# main.net
KiCad netlist of a schematic drawn in EAGLE
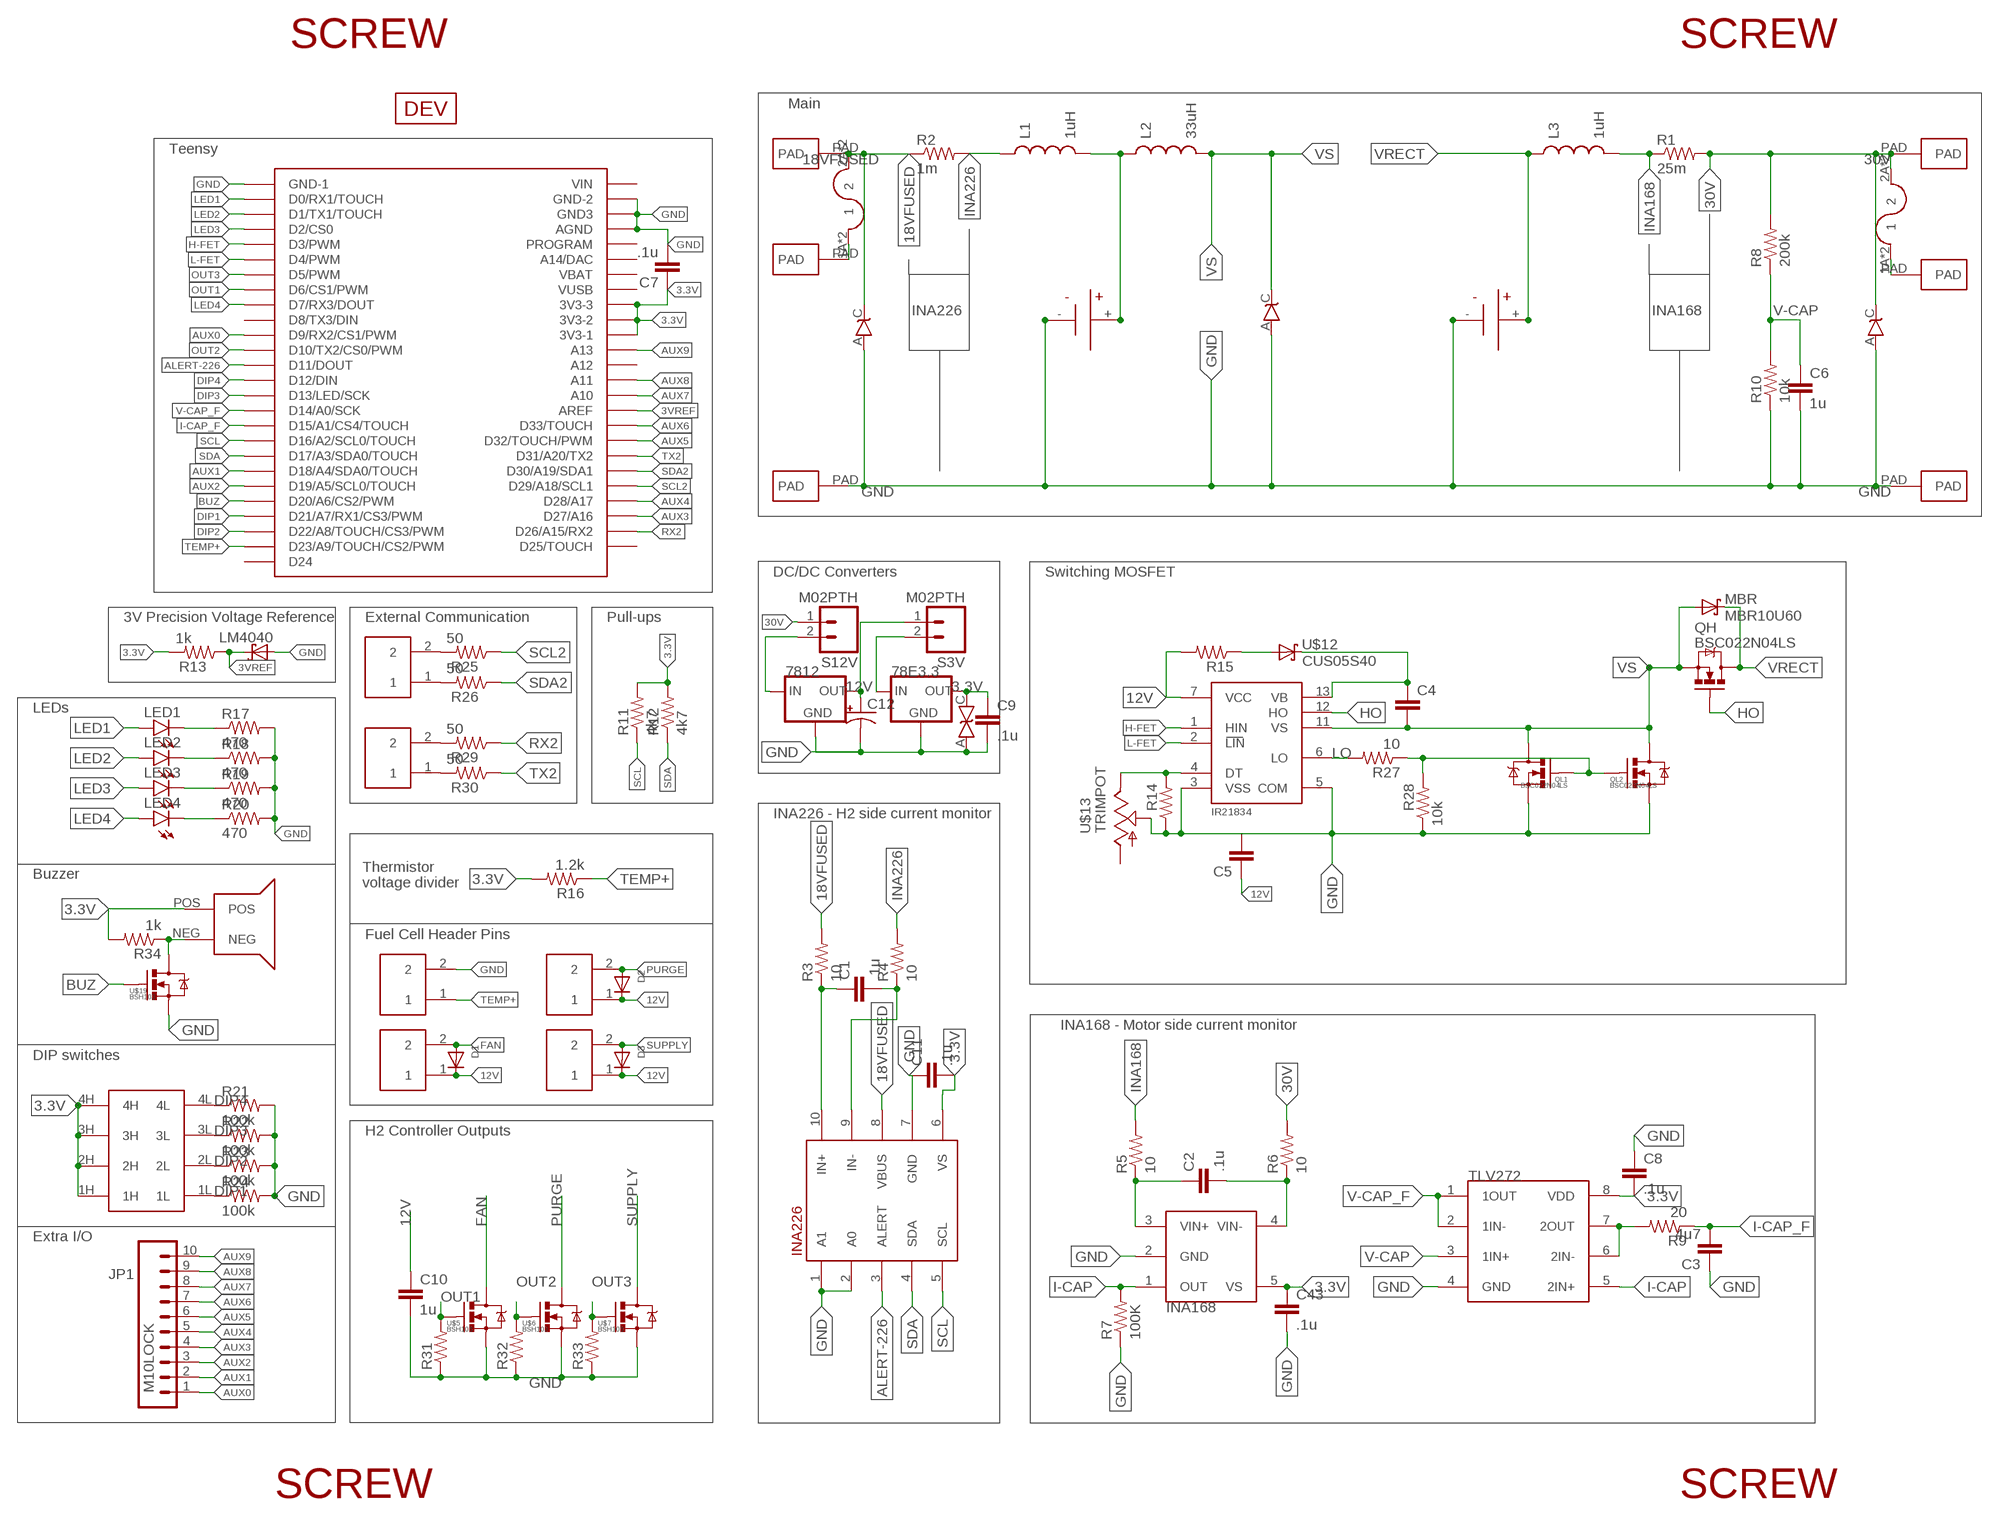
[diagram p0: schematic, sheet 1]

(export (version "E")
  (design (tool "Eeschema 10.0.6"))
  (components
    (comp (ref "78E3.3")
      (value "V_REG_78XXR-78E")
      (footprint "eagle-import:V78W")
      (libsource (lib "eagle-import") (part "V_REG_78XXR-78E"))
    )
    (comp (ref "7812")
      (value "V_REG_78XX")
      (footprint "eagle-import:V78W_BACKWARDS")
      (libsource (lib "eagle-import") (part "V_REG_78XX"))
    )
    (comp (ref "C1")
      (value ".1u")
      (footprint "eagle-import:0603-CAP")
      (libsource (lib "eagle-import") (part "CAP0603-CAP"))
    )
    (comp (ref "C1-1")
      (value "2400u")
      (footprint "eagle-import:CAP-RADIAL")
      (libsource (lib "eagle-import") (part "CAP-AL_ELECTROLYTIC"))
    )
    (comp (ref "C2")
      (value ".1u")
      (footprint "eagle-import:0603-CAP")
      (libsource (lib "eagle-import") (part "CAP0603-CAP"))
    )
    (comp (ref "C2-1")
      (value "2400u")
      (footprint "eagle-import:CAP-RADIAL")
      (libsource (lib "eagle-import") (part "CAP-AL_ELECTROLYTIC"))
    )
    (comp (ref "C3")
      (value "4u7")
      (footprint "eagle-import:0603-CAP")
      (libsource (lib "eagle-import") (part "CAP0603-CAP"))
    )
    (comp (ref "C4")
      (value "CAP0603-CAP")
      (footprint "eagle-import:0603-CAP")
      (libsource (lib "eagle-import") (part "CAP0603-CAP"))
    )
    (comp (ref "C5")
      (value "CAP0603-CAP")
      (footprint "eagle-import:0603-CAP")
      (libsource (lib "eagle-import") (part "CAP0603-CAP"))
    )
    (comp (ref "C6")
      (value "1u")
      (footprint "eagle-import:0603-CAP")
      (libsource (lib "eagle-import") (part "CAP0603-CAP"))
    )
    (comp (ref "C7")
      (value ".1u")
      (footprint "eagle-import:0603-CAP")
      (libsource (lib "eagle-import") (part "CAP0603-CAP"))
    )
    (comp (ref "C8")
      (value ".1u")
      (footprint "eagle-import:0603-CAP")
      (libsource (lib "eagle-import") (part "CAP0603-CAP"))
    )
    (comp (ref "C9")
      (value ".1u")
      (footprint "eagle-import:0603-CAP")
      (libsource (lib "eagle-import") (part "CAP0603-CAP"))
    )
    (comp (ref "C10")
      (value "1u")
      (footprint "eagle-import:0603-CAP")
      (libsource (lib "eagle-import") (part "CAP0603-CAP"))
    )
    (comp (ref "C11")
      (value ".1u")
      (footprint "eagle-import:0603-CAP")
      (libsource (lib "eagle-import") (part "CAP0603-CAP"))
    )
    (comp (ref "C12")
      (value "10UF-25V-20%(PTH)")
      (footprint "eagle-import:CPOL-RADIAL-10UF-25V")
      (libsource (lib "eagle-import") (part "10UF-25V-20%(PTH)"))
    )
    (comp (ref "C43")
      (value ".1u")
      (footprint "eagle-import:0603-CAP")
      (libsource (lib "eagle-import") (part "CAP0603-CAP"))
    )
    (comp (ref "D1")
      (value "DIODESOT23_REFLOW")
      (footprint "eagle-import:SOT23-R")
      (libsource (lib "eagle-import") (part "DIODESOT23_REFLOW"))
    )
    (comp (ref "D2")
      (value "DIODESOT23_REFLOW")
      (footprint "eagle-import:SOT23-R")
      (libsource (lib "eagle-import") (part "DIODESOT23_REFLOW"))
    )
    (comp (ref "D3")
      (value "DIODESOT23_REFLOW")
      (footprint "eagle-import:SOT23-R")
      (libsource (lib "eagle-import") (part "DIODESOT23_REFLOW"))
    )
    (comp (ref "FAN")
      (value "HEADER2")
      (footprint "eagle-import:2PINVALULOK")
      (libsource (lib "eagle-import") (part "HEADER2"))
    )
    (comp (ref "I2C")
      (value "HEADER2")
      (footprint "eagle-import:2PINVALULOK")
      (libsource (lib "eagle-import") (part "HEADER2"))
    )
    (comp (ref "INFUSE")
      (value "FUSE")
      (footprint "eagle-import:AUTO_FUSE")
      (libsource (lib "eagle-import") (part "FUSE"))
    )
    (comp (ref "JP1")
      (value "M10LOCK")
      (footprint "eagle-import:1X10_LOCK")
      (libsource (lib "eagle-import") (part "M10LOCK"))
    )
    (comp (ref "L1")
      (value "1uH")
      (footprint "eagle-import:SER20XX")
      (libsource (lib "eagle-import") (part "INDUCTORSER2010-102"))
    )
    (comp (ref "L2")
      (value "33uH")
      (footprint "eagle-import:D1787")
      (libsource (lib "eagle-import") (part "D1787-AL"))
    )
    (comp (ref "L3")
      (value "1uH")
      (footprint "eagle-import:SER20XX")
      (libsource (lib "eagle-import") (part "INDUCTORSER2010-102"))
    )
    (comp (ref "LED1")
      (value "LED0603")
      (footprint "eagle-import:LED-0603")
      (libsource (lib "eagle-import") (part "LED0603"))
    )
    (comp (ref "LED2")
      (value "LED0603")
      (footprint "eagle-import:LED-0603")
      (libsource (lib "eagle-import") (part "LED0603"))
    )
    (comp (ref "LED3")
      (value "LED0603")
      (footprint "eagle-import:LED-0603")
      (libsource (lib "eagle-import") (part "LED0603"))
    )
    (comp (ref "LED4")
      (value "LED0603")
      (footprint "eagle-import:LED-0603")
      (libsource (lib "eagle-import") (part "LED0603"))
    )
    (comp (ref "MBR")
      (value "MBR10U60")
      (footprint "eagle-import:TO-277")
      (libsource (lib "eagle-import") (part "MBR10U60"))
    )
    (comp (ref "OUTFUSE")
      (value "FUSE")
      (footprint "eagle-import:AUTO_FUSE")
      (libsource (lib "eagle-import") (part "FUSE"))
    )
    (comp (ref "PURGEVALVE")
      (value "HEADER2")
      (footprint "eagle-import:2PINVALULOK")
      (libsource (lib "eagle-import") (part "HEADER2"))
    )
    (comp (ref "QH")
      (value "BSC022N04LS")
      (footprint "eagle-import:PG-TDSON-8")
      (libsource (lib "eagle-import") (part "BSC022N04LS"))
    )
    (comp (ref "QL1")
      (value "BSC022N04LS")
      (footprint "eagle-import:PG-TDSON-8")
      (libsource (lib "eagle-import") (part "BSC022N04LS"))
    )
    (comp (ref "QL2")
      (value "BSC022N04LS")
      (footprint "eagle-import:PG-TDSON-8")
      (libsource (lib "eagle-import") (part "BSC022N04LS"))
    )
    (comp (ref "R1")
      (value "25m")
      (footprint "eagle-import:R2512")
      (libsource (lib "eagle-import") (part "RESISTOR2512"))
    )
    (comp (ref "R2")
      (value "1m")
      (footprint "eagle-import:R2512")
      (libsource (lib "eagle-import") (part "RESISTOR2512"))
    )
    (comp (ref "R3")
      (value "10")
      (footprint "eagle-import:0603-RES")
      (libsource (lib "eagle-import") (part "RESISTOR0603-RES"))
    )
    (comp (ref "R4")
      (value "10")
      (footprint "eagle-import:0603-RES")
      (libsource (lib "eagle-import") (part "RESISTOR0603-RES"))
    )
    (comp (ref "R5")
      (value "10")
      (footprint "eagle-import:0603-RES")
      (libsource (lib "eagle-import") (part "RESISTOR0603-RES"))
    )
    (comp (ref "R6")
      (value "10")
      (footprint "eagle-import:0603-RES")
      (libsource (lib "eagle-import") (part "RESISTOR0603-RES"))
    )
    (comp (ref "R7")
      (value "100K")
      (footprint "eagle-import:0603-RES")
      (libsource (lib "eagle-import") (part "RESISTOR0603-RES"))
    )
    (comp (ref "R8")
      (value "200k")
      (footprint "eagle-import:0603-RES")
      (libsource (lib "eagle-import") (part "RESISTOR0603-RES"))
    )
    (comp (ref "R9")
      (value "20")
      (footprint "eagle-import:0603-RES")
      (libsource (lib "eagle-import") (part "RESISTOR0603-RES"))
    )
    (comp (ref "R10")
      (value "10k")
      (footprint "eagle-import:0603-RES")
      (libsource (lib "eagle-import") (part "RESISTOR0603-RES"))
    )
    (comp (ref "R11")
      (value "4k7")
      (footprint "eagle-import:0603-RES")
      (libsource (lib "eagle-import") (part "RESISTOR0603-RES"))
    )
    (comp (ref "R12")
      (value "4k7")
      (footprint "eagle-import:0603-RES")
      (libsource (lib "eagle-import") (part "RESISTOR0603-RES"))
    )
    (comp (ref "R13")
      (value "1k")
      (footprint "eagle-import:0603-RES")
      (libsource (lib "eagle-import") (part "RESISTOR0603-RES"))
    )
    (comp (ref "R14")
      (value "RESISTOR0603-RES")
      (footprint "eagle-import:0603-RES")
      (libsource (lib "eagle-import") (part "RESISTOR0603-RES"))
    )
    (comp (ref "R15")
      (value "RESISTOR0603-RES")
      (footprint "eagle-import:0603-RES")
      (libsource (lib "eagle-import") (part "RESISTOR0603-RES"))
    )
    (comp (ref "R16")
      (value "1.2k")
      (footprint "eagle-import:0603-RES")
      (libsource (lib "eagle-import") (part "RESISTOR0603-RES"))
    )
    (comp (ref "R17")
      (value "470")
      (footprint "eagle-import:0603-RES")
      (libsource (lib "eagle-import") (part "RESISTOR0603-RES"))
    )
    (comp (ref "R18")
      (value "470")
      (footprint "eagle-import:0603-RES")
      (libsource (lib "eagle-import") (part "RESISTOR0603-RES"))
    )
    (comp (ref "R19")
      (value "470")
      (footprint "eagle-import:0603-RES")
      (libsource (lib "eagle-import") (part "RESISTOR0603-RES"))
    )
    (comp (ref "R20")
      (value "470")
      (footprint "eagle-import:0603-RES")
      (libsource (lib "eagle-import") (part "RESISTOR0603-RES"))
    )
    (comp (ref "R21")
      (value "100k")
      (footprint "eagle-import:0603-RES")
      (libsource (lib "eagle-import") (part "RESISTOR0603-RES"))
    )
    (comp (ref "R22")
      (value "100k")
      (footprint "eagle-import:0603-RES")
      (libsource (lib "eagle-import") (part "RESISTOR0603-RES"))
    )
    (comp (ref "R23")
      (value "100k")
      (footprint "eagle-import:0603-RES")
      (libsource (lib "eagle-import") (part "RESISTOR0603-RES"))
    )
    (comp (ref "R24")
      (value "100k")
      (footprint "eagle-import:0603-RES")
      (libsource (lib "eagle-import") (part "RESISTOR0603-RES"))
    )
    (comp (ref "R25")
      (value "50")
      (footprint "eagle-import:0603-RES")
      (libsource (lib "eagle-import") (part "RESISTOR0603-RES"))
    )
    (comp (ref "R26")
      (value "50")
      (footprint "eagle-import:0603-RES")
      (libsource (lib "eagle-import") (part "RESISTOR0603-RES"))
    )
    (comp (ref "R27")
      (value "10")
      (footprint "eagle-import:0402-RES")
      (libsource (lib "eagle-import") (part "RESISTOR0402-RES"))
    )
    (comp (ref "R28")
      (value "10k")
      (footprint "eagle-import:0603-RES")
      (libsource (lib "eagle-import") (part "RESISTOR0603-RES"))
    )
    (comp (ref "R29")
      (value "50")
      (footprint "eagle-import:0603-RES")
      (libsource (lib "eagle-import") (part "RESISTOR0603-RES"))
    )
    (comp (ref "R30")
      (value "50")
      (footprint "eagle-import:0603-RES")
      (libsource (lib "eagle-import") (part "RESISTOR0603-RES"))
    )
    (comp (ref "R31")
      (value "RESISTOR0603-RES")
      (footprint "eagle-import:0603-RES")
      (libsource (lib "eagle-import") (part "RESISTOR0603-RES"))
    )
    (comp (ref "R32")
      (value "RESISTOR0603-RES")
      (footprint "eagle-import:0603-RES")
      (libsource (lib "eagle-import") (part "RESISTOR0603-RES"))
    )
    (comp (ref "R33")
      (value "RESISTOR0603-RES")
      (footprint "eagle-import:0603-RES")
      (libsource (lib "eagle-import") (part "RESISTOR0603-RES"))
    )
    (comp (ref "R34")
      (value "1k")
      (footprint "eagle-import:0603-RES")
      (libsource (lib "eagle-import") (part "RESISTOR0603-RES"))
    )
    (comp (ref "S3V")
      (value "M02PTH")
      (footprint "eagle-import:1X02")
      (libsource (lib "eagle-import") (part "M02PTH"))
    )
    (comp (ref "S12V")
      (value "M02PTH")
      (footprint "eagle-import:1X02")
      (libsource (lib "eagle-import") (part "M02PTH"))
    )
    (comp (ref "SERIAL2")
      (value "HEADER2")
      (footprint "eagle-import:2PINVALULOK")
      (libsource (lib "eagle-import") (part "HEADER2"))
    )
    (comp (ref "SUPPLYVALVE")
      (value "HEADER2")
      (footprint "eagle-import:2PINVALULOK")
      (libsource (lib "eagle-import") (part "HEADER2"))
    )
    (comp (ref "THERMISTOR")
      (value "HEADER2")
      (footprint "eagle-import:2PINVALULOK")
      (libsource (lib "eagle-import") (part "HEADER2"))
    )
    (comp (ref "TVS1")
      (value "TVS_UNIDO-214AB")
      (footprint "eagle-import:DO-214AB")
      (libsource (lib "eagle-import") (part "TVS_UNIDO-214AB"))
    )
    (comp (ref "TVS2")
      (value "TVS_UNIDO-214AB")
      (footprint "eagle-import:DO-214AB")
      (libsource (lib "eagle-import") (part "TVS_UNIDO-214AB"))
    )
    (comp (ref "TVS3")
      (value "TVS_UNIDO-214AB")
      (footprint "eagle-import:DO-214AB")
      (libsource (lib "eagle-import") (part "TVS_UNIDO-214AB"))
    )
    (comp (ref "TVS4")
      (value "3.3V")
      (footprint "eagle-import:SOD-523")
      (libsource (lib "eagle-import") (part "TVS_BISOD-523"))
    )
    (comp (ref "U$1")
      (value "PAD")
      (footprint "eagle-import:PAD")
      (libsource (lib "eagle-import") (part "PAD"))
    )
    (comp (ref "U$2")
      (value "PAD")
      (footprint "eagle-import:PAD")
      (libsource (lib "eagle-import") (part "PAD"))
    )
    (comp (ref "U$3")
      (value "PAD")
      (footprint "eagle-import:PAD")
      (libsource (lib "eagle-import") (part "PAD"))
    )
    (comp (ref "U$5")
      (value "BSH103")
      (footprint "eagle-import:SOT23-3")
      (libsource (lib "eagle-import") (part "BSH103"))
    )
    (comp (ref "U$6")
      (value "BSH103")
      (footprint "eagle-import:SOT23-3")
      (libsource (lib "eagle-import") (part "BSH103"))
    )
    (comp (ref "U$7")
      (value "BSH103")
      (footprint "eagle-import:SOT23-3")
      (libsource (lib "eagle-import") (part "BSH103"))
    )
    (comp (ref "U$8")
      (value "SCREW")
      (footprint "eagle-import:M3HOLE")
      (libsource (lib "eagle-import") (part "SCREW"))
    )
    (comp (ref "U$9")
      (value "IR21834")
      (footprint "eagle-import:SO14")
      (libsource (lib "eagle-import") (part "IR21834"))
    )
    (comp (ref "U$10")
      (value "PAD")
      (footprint "eagle-import:PAD")
      (libsource (lib "eagle-import") (part "PAD"))
    )
    (comp (ref "U$11")
      (value "SCREW")
      (footprint "eagle-import:M3HOLE")
      (libsource (lib "eagle-import") (part "SCREW"))
    )
    (comp (ref "U$12")
      (value "CUS05S40")
      (footprint "eagle-import:SOD323_ST")
      (libsource (lib "eagle-import") (part "CUS05S40"))
    )
    (comp (ref "U$13")
      (value "TRIMPOT")
      (footprint "eagle-import:3MM_TRIMM")
      (libsource (lib "eagle-import") (part "TRIMPOT"))
    )
    (comp (ref "U$14")
      (value "LM4040")
      (footprint "eagle-import:SOT23-3")
      (libsource (lib "eagle-import") (part "LM4040"))
    )
    (comp (ref "U$16")
      (value "PAD")
      (footprint "eagle-import:PAD")
      (libsource (lib "eagle-import") (part "PAD"))
    )
    (comp (ref "U$17")
      (value "SCREW")
      (footprint "eagle-import:M3HOLE")
      (libsource (lib "eagle-import") (part "SCREW"))
    )
    (comp (ref "U$18")
      (value "BUZZER12MM")
      (footprint "eagle-import:BUZZER_12MM")
      (libsource (lib "eagle-import") (part "BUZZER12MM"))
    )
    (comp (ref "U$19")
      (value "BSH103")
      (footprint "eagle-import:SOT23-3")
      (libsource (lib "eagle-import") (part "BSH103"))
    )
    (comp (ref "U$20")
      (value "DIP_SWITCH")
      (footprint "eagle-import:DIPSWITCH4")
      (libsource (lib "eagle-import") (part "DIP_SWITCH"))
    )
    (comp (ref "U$21")
      (value "DEV")
      (footprint "eagle-import:DEV")
      (libsource (lib "eagle-import") (part "DEV"))
    )
    (comp (ref "U$24")
      (value "PAD")
      (footprint "eagle-import:PAD")
      (libsource (lib "eagle-import") (part "PAD"))
    )
    (comp (ref "U$26")
      (value "TEENSY30-FULL")
      (footprint "eagle-import:TEENSY30-FULL")
      (libsource (lib "eagle-import") (part "TEENSY30-FULL"))
    )
    (comp (ref "U$29")
      (value "SCREW")
      (footprint "eagle-import:M3HOLE")
      (libsource (lib "eagle-import") (part "SCREW"))
    )
    (comp (ref "U1")
      (value "INA226")
      (footprint "eagle-import:PSOP-10")
      (libsource (lib "eagle-import") (part "INA226"))
    )
    (comp (ref "U2")
      (value "INA168INA168")
      (footprint "eagle-import:SOT23-5")
      (libsource (lib "eagle-import") (part "INA168INA168"))
    )
    (comp (ref "U3")
      (value "TLV272")
      (footprint "eagle-import:8-VSSOP")
      (libsource (lib "eagle-import") (part "TLV272"))
    )
  )
  (nets
    (net (code "1") (name "/LO") (class "Default")
      (node (ref "QL1") (pin "4") (pinfunction "G_4") (pintype "passive"))
      (node (ref "QL2") (pin "4") (pinfunction "G_4") (pintype "passive"))
      (node (ref "R27") (pin "1") (pinfunction "1_1") (pintype "passive"))
      (node (ref "R28") (pin "2") (pinfunction "2_2") (pintype "passive"))
    )
    (net (code "2") (name "3.3V") (class "Default")
      (node (ref "78E3.3") (pin "OUT") (pinfunction "OUT_OUT") (pintype "output"))
      (node (ref "C11") (pin "2") (pinfunction "2_2") (pintype "passive"))
      (node (ref "C43") (pin "1") (pinfunction "1_1") (pintype "passive"))
      (node (ref "C7") (pin "1") (pinfunction "1_1") (pintype "passive"))
      (node (ref "C8") (pin "2") (pinfunction "2_2") (pintype "passive"))
      (node (ref "C9") (pin "1") (pinfunction "1_1") (pintype "passive"))
      (node (ref "R11") (pin "2") (pinfunction "2_2") (pintype "passive"))
      (node (ref "R12") (pin "2") (pinfunction "2_2") (pintype "passive"))
      (node (ref "R13") (pin "2") (pinfunction "2_2") (pintype "passive"))
      (node (ref "R16") (pin "2") (pinfunction "2_2") (pintype "passive"))
      (node (ref "R34") (pin "2") (pinfunction "2_2") (pintype "passive"))
      (node (ref "TVS4") (pin "C") (pinfunction "2_C") (pintype "bidirectional"))
      (node (ref "U$18") (pin "POS") (pinfunction "POS_POS") (pintype "bidirectional"))
      (node (ref "U$20") (pin "1H") (pinfunction "1H_1H") (pintype "bidirectional"))
      (node (ref "U$20") (pin "2H") (pinfunction "2H_2H") (pintype "bidirectional"))
      (node (ref "U$20") (pin "3H") (pinfunction "3H_3H") (pintype "bidirectional"))
      (node (ref "U$20") (pin "4H") (pinfunction "4H_4H") (pintype "bidirectional"))
      (node (ref "U$26") (pin "3V3") (pinfunction "3V3-1_3V3") (pintype "bidirectional"))
      (node (ref "U$26") (pin "3V3-1") (pinfunction "3V3-2_3V3-1") (pintype "bidirectional"))
      (node (ref "U$26") (pin "3V3-2") (pinfunction "3V3-3_3V3-2") (pintype "bidirectional"))
      (node (ref "U1") (pin "6") (pinfunction "VS_6") (pintype "bidirectional"))
      (node (ref "U2") (pin "5") (pinfunction "VS_5") (pintype "bidirectional"))
      (node (ref "U3") (pin "8") (pinfunction "VDD_8") (pintype "bidirectional"))
    )
    (net (code "3") (name "3VREF") (class "Default")
      (node (ref "R13") (pin "1") (pinfunction "1_1") (pintype "passive"))
      (node (ref "U$14") (pin "1") (pinfunction "C_1") (pintype "passive"))
      (node (ref "U$26") (pin "AREF") (pinfunction "AREF_AREF") (pintype "bidirectional"))
    )
    (net (code "4") (name "12V") (class "Default")
      (node (ref "7812") (pin "OUT") (pinfunction "OUT_OUT") (pintype "output"))
      (node (ref "C10") (pin "1") (pinfunction "1_1") (pintype "passive"))
      (node (ref "C12") (pin "1") (pinfunction "+_1") (pintype "passive"))
      (node (ref "C5") (pin "1") (pinfunction "1_1") (pintype "passive"))
      (node (ref "D1") (pin "3") (pinfunction "C_3") (pintype "passive"))
      (node (ref "D2") (pin "3") (pinfunction "C_3") (pintype "passive"))
      (node (ref "D3") (pin "3") (pinfunction "C_3") (pintype "passive"))
      (node (ref "FAN") (pin "1") (pinfunction "1_1") (pintype "bidirectional"))
      (node (ref "PURGEVALVE") (pin "1") (pinfunction "1_1") (pintype "bidirectional"))
      (node (ref "R15") (pin "2") (pinfunction "2_2") (pintype "passive"))
      (node (ref "S3V") (pin "1") (pinfunction "1_1") (pintype "passive"))
      (node (ref "SUPPLYVALVE") (pin "1") (pinfunction "1_1") (pintype "bidirectional"))
      (node (ref "U$9") (pin "7") (pinfunction "VCC_7") (pintype "bidirectional"))
    )
    (net (code "5") (name "18VFUSED") (class "Default")
      (node (ref "INFUSE") (pin "2A") (pinfunction "2_2A") (pintype "bidirectional"))
      (node (ref "INFUSE") (pin "2B") (pinfunction "2_2B") (pintype "bidirectional"))
      (node (ref "R2") (pin "1") (pinfunction "1_1") (pintype "passive"))
      (node (ref "R3") (pin "2") (pinfunction "2_2") (pintype "passive"))
      (node (ref "TVS1") (pin "C") (pinfunction "C_C") (pintype "bidirectional"))
      (node (ref "U$3") (pin "PAD") (pinfunction "PAD_PAD") (pintype "bidirectional"))
      (node (ref "U1") (pin "8") (pinfunction "VBUS_8") (pintype "bidirectional"))
    )
    (net (code "6") (name "30V") (class "Default")
      (node (ref "OUTFUSE") (pin "2A") (pinfunction "2_2A") (pintype "bidirectional"))
      (node (ref "OUTFUSE") (pin "2B") (pinfunction "2_2B") (pintype "bidirectional"))
      (node (ref "R1") (pin "2") (pinfunction "2_2") (pintype "passive"))
      (node (ref "R6") (pin "2") (pinfunction "2_2") (pintype "passive"))
      (node (ref "R8") (pin "2") (pinfunction "2_2") (pintype "passive"))
      (node (ref "S12V") (pin "1") (pinfunction "1_1") (pintype "passive"))
      (node (ref "TVS3") (pin "C") (pinfunction "C_C") (pintype "bidirectional"))
      (node (ref "U$1") (pin "PAD") (pinfunction "PAD_PAD") (pintype "bidirectional"))
    )
    (net (code "7") (name "ALERT-226") (class "Default")
      (node (ref "U$26") (pin "D11/DOUT") (pinfunction "D11/DOUT_D11/DOUT") (pintype "bidirectional"))
      (node (ref "U1") (pin "3") (pinfunction "ALERT_3") (pintype "bidirectional"))
    )
    (net (code "8") (name "AUX0") (class "Default")
      (node (ref "JP1") (pin "1") (pinfunction "1_1") (pintype "passive"))
      (node (ref "U$26") (pin "D9/RX2/CS1/PWM") (pinfunction "D9/RX2/CS1/PWM_D9/RX2/CS1/PWM") (pintype "bidirectional"))
    )
    (net (code "9") (name "AUX1") (class "Default")
      (node (ref "JP1") (pin "2") (pinfunction "2_2") (pintype "passive"))
      (node (ref "U$26") (pin "D18/A4/SDA/TOUCH") (pinfunction "D18/A4/SDA0/TOUCH_D18/A4/SDA/TOUCH") (pintype "bidirectional"))
    )
    (net (code "10") (name "AUX2") (class "Default")
      (node (ref "JP1") (pin "3") (pinfunction "3_3") (pintype "passive"))
      (node (ref "U$26") (pin "D19/A5/SCL/TOUCH") (pinfunction "D19/A5/SCL0/TOUCH_D19/A5/SCL/TOUCH") (pintype "bidirectional"))
    )
    (net (code "11") (name "AUX3") (class "Default")
      (node (ref "JP1") (pin "4") (pinfunction "4_4") (pintype "passive"))
      (node (ref "U$26") (pin "D27") (pinfunction "D27/A16_D27") (pintype "bidirectional"))
    )
    (net (code "12") (name "AUX4") (class "Default")
      (node (ref "JP1") (pin "5") (pinfunction "5_5") (pintype "passive"))
      (node (ref "U$26") (pin "D28") (pinfunction "D28/A17_D28") (pintype "bidirectional"))
    )
    (net (code "13") (name "AUX5") (class "Default")
      (node (ref "JP1") (pin "6") (pinfunction "6_6") (pintype "passive"))
      (node (ref "U$26") (pin "D32/TOUCH") (pinfunction "D32/TOUCH/PWM_D32/TOUCH") (pintype "bidirectional"))
    )
    (net (code "14") (name "AUX6") (class "Default")
      (node (ref "JP1") (pin "7") (pinfunction "7_7") (pintype "passive"))
      (node (ref "U$26") (pin "D33/TOUCH") (pinfunction "D33/TOUCH_D33/TOUCH") (pintype "bidirectional"))
    )
    (net (code "15") (name "AUX7") (class "Default")
      (node (ref "JP1") (pin "8") (pinfunction "8_8") (pintype "passive"))
      (node (ref "U$26") (pin "A10") (pinfunction "A10_A10") (pintype "bidirectional"))
    )
    (net (code "16") (name "AUX8") (class "Default")
      (node (ref "JP1") (pin "9") (pinfunction "9_9") (pintype "passive"))
      (node (ref "U$26") (pin "A11") (pinfunction "A11_A11") (pintype "bidirectional"))
    )
    (net (code "17") (name "AUX9") (class "Default")
      (node (ref "JP1") (pin "10") (pinfunction "10_10") (pintype "passive"))
      (node (ref "U$26") (pin "A13") (pinfunction "A13_A13") (pintype "bidirectional"))
    )
    (net (code "18") (name "BUZ") (class "Default")
      (node (ref "U$19") (pin "1") (pinfunction "G_1") (pintype "passive"))
      (node (ref "U$26") (pin "D20/A6/CS2/PWM") (pinfunction "D20/A6/CS2/PWM_D20/A6/CS2/PWM") (pintype "bidirectional"))
    )
    (net (code "19") (name "DIP1") (class "Default")
      (node (ref "R24") (pin "1") (pinfunction "1_1") (pintype "passive"))
      (node (ref "U$20") (pin "1L") (pinfunction "1L_1L") (pintype "bidirectional"))
      (node (ref "U$26") (pin "D21/A7/RX1/CS3/PWM") (pinfunction "D21/A7/RX1/CS3/PWM_D21/A7/RX1/CS3/PWM") (pintype "bidirectional"))
    )
    (net (code "20") (name "DIP2") (class "Default")
      (node (ref "R23") (pin "1") (pinfunction "1_1") (pintype "passive"))
      (node (ref "U$20") (pin "2L") (pinfunction "2L_2L") (pintype "bidirectional"))
      (node (ref "U$26") (pin "D22/A8/TOUCH/CS3/PWM") (pinfunction "D22/A8/TOUCH/CS3/PWM_D22/A8/TOUCH/CS3/PWM") (pintype "bidirectional"))
    )
    (net (code "21") (name "DIP3") (class "Default")
      (node (ref "R22") (pin "1") (pinfunction "1_1") (pintype "passive"))
      (node (ref "U$20") (pin "3L") (pinfunction "3L_3L") (pintype "bidirectional"))
      (node (ref "U$26") (pin "D13/LED/SCK") (pinfunction "D13/LED/SCK_D13/LED/SCK") (pintype "bidirectional"))
    )
    (net (code "22") (name "DIP4") (class "Default")
      (node (ref "R21") (pin "1") (pinfunction "1_1") (pintype "passive"))
      (node (ref "U$20") (pin "4L") (pinfunction "4L_4L") (pintype "bidirectional"))
      (node (ref "U$26") (pin "D12/DIN") (pinfunction "D12/DIN_D12/DIN") (pintype "bidirectional"))
    )
    (net (code "23") (name "FAN") (class "Default")
      (node (ref "D1") (pin "1") (pinfunction "A_1") (pintype "passive"))
      (node (ref "FAN") (pin "2") (pinfunction "2_2") (pintype "bidirectional"))
      (node (ref "U$5") (pin "3") (pinfunction "D_3") (pintype "passive"))
    )
    (net (code "24") (name "GND") (class "Default")
      (node (ref "7812") (pin "GND") (pinfunction "GND_GND") (pintype "input"))
      (node (ref "78E3.3") (pin "GND") (pinfunction "GND_GND") (pintype "input"))
      (node (ref "C1-1") (pin "-") (pinfunction "V-_-") (pintype "bidirectional"))
      (node (ref "C10") (pin "2") (pinfunction "2_2") (pintype "passive"))
      (node (ref "C11") (pin "1") (pinfunction "1_1") (pintype "passive"))
      (node (ref "C12") (pin "2") (pinfunction "-_2") (pintype "passive"))
      (node (ref "C2-1") (pin "-") (pinfunction "V-_-") (pintype "bidirectional"))
      (node (ref "C3") (pin "1") (pinfunction "1_1") (pintype "passive"))
      (node (ref "C43") (pin "2") (pinfunction "2_2") (pintype "passive"))
      (node (ref "C5") (pin "2") (pinfunction "2_2") (pintype "passive"))
      (node (ref "C6") (pin "2") (pinfunction "2_2") (pintype "passive"))
      (node (ref "C7") (pin "2") (pinfunction "2_2") (pintype "passive"))
      (node (ref "C8") (pin "1") (pinfunction "1_1") (pintype "passive"))
      (node (ref "C9") (pin "2") (pinfunction "2_2") (pintype "passive"))
      (node (ref "QL1") (pin "1") (pinfunction "S_1") (pintype "passive"))
      (node (ref "QL1") (pin "2") (pinfunction "S_2") (pintype "passive"))
      (node (ref "QL1") (pin "3") (pinfunction "S_3") (pintype "passive"))
      (node (ref "QL2") (pin "1") (pinfunction "S_1") (pintype "passive"))
      (node (ref "QL2") (pin "2") (pinfunction "S_2") (pintype "passive"))
      (node (ref "QL2") (pin "3") (pinfunction "S_3") (pintype "passive"))
      (node (ref "R10") (pin "1") (pinfunction "1_1") (pintype "passive"))
      (node (ref "R14") (pin "1") (pinfunction "1_1") (pintype "passive"))
      (node (ref "R17") (pin "2") (pinfunction "2_2") (pintype "passive"))
      (node (ref "R18") (pin "2") (pinfunction "2_2") (pintype "passive"))
      (node (ref "R19") (pin "2") (pinfunction "2_2") (pintype "passive"))
      (node (ref "R20") (pin "2") (pinfunction "2_2") (pintype "passive"))
      (node (ref "R21") (pin "2") (pinfunction "2_2") (pintype "passive"))
      (node (ref "R22") (pin "2") (pinfunction "2_2") (pintype "passive"))
      (node (ref "R23") (pin "2") (pinfunction "2_2") (pintype "passive"))
      (node (ref "R24") (pin "2") (pinfunction "2_2") (pintype "passive"))
      (node (ref "R28") (pin "1") (pinfunction "1_1") (pintype "passive"))
      (node (ref "R31") (pin "1") (pinfunction "1_1") (pintype "passive"))
      (node (ref "R32") (pin "1") (pinfunction "1_1") (pintype "passive"))
      (node (ref "R33") (pin "1") (pinfunction "1_1") (pintype "passive"))
      (node (ref "R7") (pin "1") (pinfunction "1_1") (pintype "passive"))
      (node (ref "THERMISTOR") (pin "2") (pinfunction "2_2") (pintype "bidirectional"))
      (node (ref "TVS1") (pin "A") (pinfunction "A_A") (pintype "bidirectional"))
      (node (ref "TVS2") (pin "A") (pinfunction "A_A") (pintype "bidirectional"))
      (node (ref "TVS3") (pin "A") (pinfunction "A_A") (pintype "bidirectional"))
      (node (ref "TVS4") (pin "A") (pinfunction "1_A") (pintype "bidirectional"))
      (node (ref "U$10") (pin "PAD") (pinfunction "PAD_PAD") (pintype "bidirectional"))
      (node (ref "U$13") (pin "2") (pinfunction "S_2") (pintype "passive"))
      (node (ref "U$14") (pin "2") (pinfunction "A_2") (pintype "passive"))
      (node (ref "U$19") (pin "2") (pinfunction "S_2") (pintype "passive"))
      (node (ref "U$2") (pin "PAD") (pinfunction "PAD_PAD") (pintype "bidirectional"))
      (node (ref "U$26") (pin "AGND") (pinfunction "AGND_AGND") (pintype "bidirectional"))
      (node (ref "U$26") (pin "GND-1") (pinfunction "GND-1_GND-1") (pintype "bidirectional"))
      (node (ref "U$26") (pin "GND-2") (pinfunction "GND-2_GND-2") (pintype "bidirectional"))
      (node (ref "U$26") (pin "GND-3") (pinfunction "GND3_GND-3") (pintype "bidirectional"))
      (node (ref "U$5") (pin "2") (pinfunction "S_2") (pintype "passive"))
      (node (ref "U$6") (pin "2") (pinfunction "S_2") (pintype "passive"))
      (node (ref "U$7") (pin "2") (pinfunction "S_2") (pintype "passive"))
      (node (ref "U$9") (pin "3") (pinfunction "VSS_3") (pintype "bidirectional"))
      (node (ref "U$9") (pin "5") (pinfunction "COM_5") (pintype "bidirectional"))
      (node (ref "U1") (pin "1") (pinfunction "A1_1") (pintype "bidirectional"))
      (node (ref "U1") (pin "2") (pinfunction "A0_2") (pintype "bidirectional"))
      (node (ref "U1") (pin "7") (pinfunction "GND_7") (pintype "bidirectional"))
      (node (ref "U2") (pin "2") (pinfunction "GND_2") (pintype "bidirectional"))
      (node (ref "U3") (pin "4") (pinfunction "GND_4") (pintype "bidirectional"))
    )
    (net (code "25") (name "H-FET") (class "Default")
      (node (ref "U$26") (pin "D3/PWM") (pinfunction "D3/PWM_D3/PWM") (pintype "bidirectional"))
      (node (ref "U$9") (pin "1") (pinfunction "HIN_1") (pintype "bidirectional"))
    )
    (net (code "26") (name "HO") (class "Default")
      (node (ref "QH") (pin "4") (pinfunction "G_4") (pintype "passive"))
      (node (ref "U$9") (pin "12") (pinfunction "HO_12") (pintype "bidirectional"))
    )
    (net (code "27") (name "I-CAP") (class "Default")
      (node (ref "R7") (pin "2") (pinfunction "2_2") (pintype "passive"))
      (node (ref "U2") (pin "1") (pinfunction "OUT_1") (pintype "bidirectional"))
      (node (ref "U3") (pin "5") (pinfunction "2IN+_5") (pintype "bidirectional"))
    )
    (net (code "28") (name "I-CAP_F") (class "Default")
      (node (ref "C3") (pin "2") (pinfunction "2_2") (pintype "passive"))
      (node (ref "R9") (pin "1") (pinfunction "1_1") (pintype "passive"))
      (node (ref "U$26") (pin "D15/A1/CS4/TOUCH") (pinfunction "D15/A1/CS4/TOUCH_D15/A1/CS4/TOUCH") (pintype "bidirectional"))
    )
    (net (code "29") (name "INA168") (class "Default")
      (node (ref "L3") (pin "1") (pinfunction "0_1") (pintype "bidirectional"))
      (node (ref "R1") (pin "1") (pinfunction "1_1") (pintype "passive"))
      (node (ref "R5") (pin "2") (pinfunction "2_2") (pintype "passive"))
    )
    (net (code "30") (name "INA226") (class "Default")
      (node (ref "L1") (pin "2") (pinfunction "1_2") (pintype "bidirectional"))
      (node (ref "R2") (pin "2") (pinfunction "2_2") (pintype "passive"))
      (node (ref "R4") (pin "2") (pinfunction "2_2") (pintype "passive"))
    )
    (net (code "31") (name "L-FET") (class "Default")
      (node (ref "U$26") (pin "D4/PWM") (pinfunction "D4/PWM_D4/PWM") (pintype "bidirectional"))
      (node (ref "U$9") (pin "2") (pinfunction "LIN_2") (pintype "bidirectional"))
    )
    (net (code "32") (name "LED1") (class "Default")
      (node (ref "LED1") (pin "A") (pinfunction "A_A") (pintype "passive"))
      (node (ref "U$26") (pin "D0/RX1/TOUCH") (pinfunction "D0/RX1/TOUCH_D0/RX1/TOUCH") (pintype "bidirectional"))
    )
    (net (code "33") (name "LED2") (class "Default")
      (node (ref "LED2") (pin "A") (pinfunction "A_A") (pintype "passive"))
      (node (ref "U$26") (pin "D1/TX1/TOUCH") (pinfunction "D1/TX1/TOUCH_D1/TX1/TOUCH") (pintype "bidirectional"))
    )
    (net (code "34") (name "LED3") (class "Default")
      (node (ref "LED3") (pin "A") (pinfunction "A_A") (pintype "passive"))
      (node (ref "U$26") (pin "D2/CS0") (pinfunction "D2/CS0_D2/CS0") (pintype "bidirectional"))
    )
    (net (code "35") (name "LED4") (class "Default")
      (node (ref "LED4") (pin "A") (pinfunction "A_A") (pintype "passive"))
      (node (ref "U$26") (pin "D7/RX3/DOUT") (pinfunction "D7/RX3/DOUT_D7/RX3/DOUT") (pintype "bidirectional"))
    )
    (net (code "36") (name "Net-(78E3.3-PadIN)") (class "Default")
      (node (ref "78E3.3") (pin "IN") (pinfunction "IN_IN") (pintype "input"))
      (node (ref "S3V") (pin "2") (pinfunction "2_2") (pintype "passive"))
    )
    (net (code "37") (name "Net-(7812-PadIN)") (class "Default")
      (node (ref "7812") (pin "IN") (pinfunction "IN_IN") (pintype "input"))
      (node (ref "S12V") (pin "2") (pinfunction "2_2") (pintype "passive"))
    )
    (net (code "38") (name "Net-(C1-1-V+)") (class "Default")
      (node (ref "C1-1") (pin "+") (pinfunction "V+_+") (pintype "bidirectional"))
      (node (ref "L1") (pin "1") (pinfunction "0_1") (pintype "bidirectional"))
      (node (ref "L2") (pin "P$2") (pinfunction "1_P$2") (pintype "bidirectional"))
    )
    (net (code "39") (name "Net-(I2C-Pad1)") (class "Default")
      (node (ref "I2C") (pin "1") (pinfunction "1_1") (pintype "bidirectional"))
      (node (ref "R26") (pin "2") (pinfunction "2_2") (pintype "passive"))
    )
    (net (code "40") (name "Net-(I2C-Pad2)") (class "Default")
      (node (ref "I2C") (pin "2") (pinfunction "2_2") (pintype "bidirectional"))
      (node (ref "R25") (pin "2") (pinfunction "2_2") (pintype "passive"))
    )
    (net (code "41") (name "Net-(INFUSE-1-Pad1A)") (class "Default")
      (node (ref "INFUSE") (pin "1A") (pinfunction "1_1A") (pintype "bidirectional"))
      (node (ref "INFUSE") (pin "1B") (pinfunction "1_1B") (pintype "bidirectional"))
      (node (ref "U$24") (pin "PAD") (pinfunction "PAD_PAD") (pintype "bidirectional"))
    )
    (net (code "42") (name "Net-(LED1-PadC)") (class "Default")
      (node (ref "LED1") (pin "C") (pinfunction "C_C") (pintype "passive"))
      (node (ref "R17") (pin "1") (pinfunction "1_1") (pintype "passive"))
    )
    (net (code "43") (name "Net-(LED2-PadC)") (class "Default")
      (node (ref "LED2") (pin "C") (pinfunction "C_C") (pintype "passive"))
      (node (ref "R18") (pin "1") (pinfunction "1_1") (pintype "passive"))
    )
    (net (code "44") (name "Net-(LED3-PadC)") (class "Default")
      (node (ref "LED3") (pin "C") (pinfunction "C_C") (pintype "passive"))
      (node (ref "R19") (pin "1") (pinfunction "1_1") (pintype "passive"))
    )
    (net (code "45") (name "Net-(LED4-PadC)") (class "Default")
      (node (ref "LED4") (pin "C") (pinfunction "C_C") (pintype "passive"))
      (node (ref "R20") (pin "1") (pinfunction "1_1") (pintype "passive"))
    )
    (net (code "46") (name "Net-(OUTFUSE-1-Pad1A)") (class "Default")
      (node (ref "OUTFUSE") (pin "1A") (pinfunction "1_1A") (pintype "bidirectional"))
      (node (ref "OUTFUSE") (pin "1B") (pinfunction "1_1B") (pintype "bidirectional"))
      (node (ref "U$16") (pin "PAD") (pinfunction "PAD_PAD") (pintype "bidirectional"))
    )
    (net (code "47") (name "Net-(R15-Pad1)") (class "Default")
      (node (ref "R15") (pin "1") (pinfunction "1_1") (pintype "passive"))
      (node (ref "U$12") (pin "A") (pinfunction "A_A") (pintype "passive"))
    )
    (net (code "48") (name "Net-(R29-Pad2)") (class "Default")
      (node (ref "R29") (pin "2") (pinfunction "2_2") (pintype "passive"))
      (node (ref "SERIAL2") (pin "2") (pinfunction "2_2") (pintype "bidirectional"))
    )
    (net (code "49") (name "Net-(R30-Pad2)") (class "Default")
      (node (ref "R30") (pin "2") (pinfunction "2_2") (pintype "passive"))
      (node (ref "SERIAL2") (pin "1") (pinfunction "1_1") (pintype "bidirectional"))
    )
    (net (code "50") (name "Net-(U$9-LO)") (class "Default")
      (node (ref "R27") (pin "2") (pinfunction "2_2") (pintype "passive"))
      (node (ref "U$9") (pin "6") (pinfunction "LO_6") (pintype "bidirectional"))
    )
    (net (code "51") (name "Net-(U$9-VB)") (class "Default")
      (node (ref "C4") (pin "1") (pinfunction "1_1") (pintype "passive"))
      (node (ref "U$12") (pin "C") (pinfunction "C_C") (pintype "passive"))
      (node (ref "U$9") (pin "13") (pinfunction "VB_13") (pintype "bidirectional"))
    )
    (net (code "52") (name "Net-(U$13-E)") (class "Default")
      (node (ref "R14") (pin "2") (pinfunction "2_2") (pintype "passive"))
      (node (ref "U$13") (pin "3") (pinfunction "E_3") (pintype "passive"))
      (node (ref "U$9") (pin "4") (pinfunction "DT_4") (pintype "bidirectional"))
    )
    (net (code "53") (name "Net-(U$19-D)") (class "Default")
      (node (ref "R34") (pin "1") (pinfunction "1_1") (pintype "passive"))
      (node (ref "U$18") (pin "NEG") (pinfunction "NEG_NEG") (pintype "bidirectional"))
      (node (ref "U$19") (pin "3") (pinfunction "D_3") (pintype "passive"))
    )
    (net (code "54") (name "Net-(U1-IN+)") (class "Default")
      (node (ref "C1") (pin "1") (pinfunction "1_1") (pintype "passive"))
      (node (ref "R3") (pin "1") (pinfunction "1_1") (pintype "passive"))
      (node (ref "U1") (pin "10") (pinfunction "IN+_10") (pintype "bidirectional"))
    )
    (net (code "55") (name "Net-(U1-IN-)") (class "Default")
      (node (ref "C1") (pin "2") (pinfunction "2_2") (pintype "passive"))
      (node (ref "R4") (pin "1") (pinfunction "1_1") (pintype "passive"))
      (node (ref "U1") (pin "9") (pinfunction "IN-_9") (pintype "bidirectional"))
    )
    (net (code "56") (name "Net-(U2-VIN+)") (class "Default")
      (node (ref "C2") (pin "1") (pinfunction "1_1") (pintype "passive"))
      (node (ref "R5") (pin "1") (pinfunction "1_1") (pintype "passive"))
      (node (ref "U2") (pin "3") (pinfunction "VIN+_3") (pintype "bidirectional"))
    )
    (net (code "57") (name "Net-(U2-VIN-)") (class "Default")
      (node (ref "C2") (pin "2") (pinfunction "2_2") (pintype "passive"))
      (node (ref "R6") (pin "1") (pinfunction "1_1") (pintype "passive"))
      (node (ref "U2") (pin "4") (pinfunction "VIN-_4") (pintype "bidirectional"))
    )
    (net (code "58") (name "Net-(U3-2IN-)") (class "Default")
      (node (ref "R9") (pin "2") (pinfunction "2_2") (pintype "passive"))
      (node (ref "U3") (pin "6") (pinfunction "2IN-_6") (pintype "bidirectional"))
      (node (ref "U3") (pin "7") (pinfunction "2OUT_7") (pintype "bidirectional"))
    )
    (net (code "59") (name "OUT1") (class "Default")
      (node (ref "R31") (pin "2") (pinfunction "2_2") (pintype "passive"))
      (node (ref "U$26") (pin "D6/CS1/PWM") (pinfunction "D6/CS1/PWM_D6/CS1/PWM") (pintype "bidirectional"))
      (node (ref "U$5") (pin "1") (pinfunction "G_1") (pintype "passive"))
    )
    (net (code "60") (name "OUT2") (class "Default")
      (node (ref "R32") (pin "2") (pinfunction "2_2") (pintype "passive"))
      (node (ref "U$26") (pin "D10/TX2/CS0/PWM") (pinfunction "D10/TX2/CS0/PWM_D10/TX2/CS0/PWM") (pintype "bidirectional"))
      (node (ref "U$6") (pin "1") (pinfunction "G_1") (pintype "passive"))
    )
    (net (code "61") (name "OUT3") (class "Default")
      (node (ref "R33") (pin "2") (pinfunction "2_2") (pintype "passive"))
      (node (ref "U$26") (pin "D5/TX1/PWM") (pinfunction "D5/PWM_D5/TX1/PWM") (pintype "bidirectional"))
      (node (ref "U$7") (pin "1") (pinfunction "G_1") (pintype "passive"))
    )
    (net (code "62") (name "PURGE") (class "Default")
      (node (ref "D2") (pin "1") (pinfunction "A_1") (pintype "passive"))
      (node (ref "PURGEVALVE") (pin "2") (pinfunction "2_2") (pintype "bidirectional"))
      (node (ref "U$6") (pin "3") (pinfunction "D_3") (pintype "passive"))
    )
    (net (code "63") (name "RX2") (class "Default")
      (node (ref "R29") (pin "1") (pinfunction "1_1") (pintype "passive"))
      (node (ref "U$26") (pin "D26/RX2") (pinfunction "D26/A15/RX2_D26/RX2") (pintype "bidirectional"))
    )
    (net (code "64") (name "SCL") (class "Default")
      (node (ref "R11") (pin "1") (pinfunction "1_1") (pintype "passive"))
      (node (ref "U$26") (pin "D16/A2/SCL/TOUCH") (pinfunction "D16/A2/SCL0/TOUCH_D16/A2/SCL/TOUCH") (pintype "bidirectional"))
      (node (ref "U1") (pin "5") (pinfunction "SCL_5") (pintype "bidirectional"))
    )
    (net (code "65") (name "SCL2") (class "Default")
      (node (ref "R25") (pin "1") (pinfunction "1_1") (pintype "passive"))
      (node (ref "U$26") (pin "D29") (pinfunction "D29/A18/SCL1_D29") (pintype "bidirectional"))
    )
    (net (code "66") (name "SDA") (class "Default")
      (node (ref "R12") (pin "1") (pinfunction "1_1") (pintype "passive"))
      (node (ref "U$26") (pin "D17/A3/SDA/TOUCH") (pinfunction "D17/A3/SDA0/TOUCH_D17/A3/SDA/TOUCH") (pintype "bidirectional"))
      (node (ref "U1") (pin "4") (pinfunction "SDA_4") (pintype "bidirectional"))
    )
    (net (code "67") (name "SDA2") (class "Default")
      (node (ref "R26") (pin "1") (pinfunction "1_1") (pintype "passive"))
      (node (ref "U$26") (pin "D30") (pinfunction "D30/A19/SDA1_D30") (pintype "bidirectional"))
    )
    (net (code "68") (name "SUPPLY") (class "Default")
      (node (ref "D3") (pin "1") (pinfunction "A_1") (pintype "passive"))
      (node (ref "SUPPLYVALVE") (pin "2") (pinfunction "2_2") (pintype "bidirectional"))
      (node (ref "U$7") (pin "3") (pinfunction "D_3") (pintype "passive"))
    )
    (net (code "69") (name "TEMP+") (class "Default")
      (node (ref "R16") (pin "1") (pinfunction "1_1") (pintype "passive"))
      (node (ref "THERMISTOR") (pin "1") (pinfunction "1_1") (pintype "bidirectional"))
      (node (ref "U$26") (pin "D23/A9/TOUCH/CS2/PWM") (pinfunction "D23/A9/TOUCH/CS2/PWM_D23/A9/TOUCH/CS2/PWM") (pintype "bidirectional"))
    )
    (net (code "70") (name "TX2") (class "Default")
      (node (ref "R30") (pin "1") (pinfunction "1_1") (pintype "passive"))
      (node (ref "U$26") (pin "D31/TX2") (pinfunction "D31/A20/TX2_D31/TX2") (pintype "bidirectional"))
    )
    (net (code "71") (name "V-CAP") (class "Default")
      (node (ref "C6") (pin "1") (pinfunction "1_1") (pintype "passive"))
      (node (ref "R10") (pin "2") (pinfunction "2_2") (pintype "passive"))
      (node (ref "R8") (pin "1") (pinfunction "1_1") (pintype "passive"))
      (node (ref "U3") (pin "3") (pinfunction "1IN+_3") (pintype "bidirectional"))
    )
    (net (code "72") (name "V-CAP_F") (class "Default")
      (node (ref "U$26") (pin "D14/A0/SCK") (pinfunction "D14/A0/SCK_D14/A0/SCK") (pintype "bidirectional"))
      (node (ref "U3") (pin "1") (pinfunction "1OUT_1") (pintype "bidirectional"))
      (node (ref "U3") (pin "2") (pinfunction "1IN-_2") (pintype "bidirectional"))
    )
    (net (code "73") (name "VRECT") (class "Default")
      (node (ref "C2-1") (pin "+") (pinfunction "V+_+") (pintype "bidirectional"))
      (node (ref "L3") (pin "2") (pinfunction "1_2") (pintype "bidirectional"))
      (node (ref "MBR") (pin "3") (pinfunction "C_3") (pintype "passive"))
      (node (ref "QH") (pin "5") (pinfunction "D_5") (pintype "passive"))
      (node (ref "QH") (pin "6") (pinfunction "D_6") (pintype "passive"))
      (node (ref "QH") (pin "7") (pinfunction "D_7") (pintype "passive"))
      (node (ref "QH") (pin "8") (pinfunction "D_8") (pintype "passive"))
      (node (ref "QH") (pin "TH") (pinfunction "D_TH") (pintype "passive"))
    )
    (net (code "74") (name "VS") (class "Default")
      (node (ref "C4") (pin "2") (pinfunction "2_2") (pintype "passive"))
      (node (ref "L2") (pin "P$1") (pinfunction "0_P$1") (pintype "bidirectional"))
      (node (ref "MBR") (pin "1") (pinfunction "A_1") (pintype "passive"))
      (node (ref "MBR") (pin "2") (pinfunction "A_2") (pintype "passive"))
      (node (ref "QH") (pin "1") (pinfunction "S_1") (pintype "passive"))
      (node (ref "QH") (pin "2") (pinfunction "S_2") (pintype "passive"))
      (node (ref "QH") (pin "3") (pinfunction "S_3") (pintype "passive"))
      (node (ref "QL1") (pin "5") (pinfunction "D_5") (pintype "passive"))
      (node (ref "QL1") (pin "6") (pinfunction "D_6") (pintype "passive"))
      (node (ref "QL1") (pin "7") (pinfunction "D_7") (pintype "passive"))
      (node (ref "QL1") (pin "8") (pinfunction "D_8") (pintype "passive"))
      (node (ref "QL1") (pin "TH") (pinfunction "D_TH") (pintype "passive"))
      (node (ref "QL2") (pin "5") (pinfunction "D_5") (pintype "passive"))
      (node (ref "QL2") (pin "6") (pinfunction "D_6") (pintype "passive"))
      (node (ref "QL2") (pin "7") (pinfunction "D_7") (pintype "passive"))
      (node (ref "QL2") (pin "8") (pinfunction "D_8") (pintype "passive"))
      (node (ref "QL2") (pin "TH") (pinfunction "D_TH") (pintype "passive"))
      (node (ref "TVS2") (pin "C") (pinfunction "C_C") (pintype "bidirectional"))
      (node (ref "U$9") (pin "11") (pinfunction "VS_11") (pintype "bidirectional"))
    )
    (net (code "75") (name "unconnected-(U$13-A-Pad1)") (class "Default")
      (node (ref "U$13") (pin "1") (pinfunction "A_1") (pintype "passive"))
    )
    (net (code "76") (name "unconnected-(U$26-PadA12)") (class "Default")
      (node (ref "U$26") (pin "A12") (pinfunction "A12_A12") (pintype "bidirectional"))
    )
    (net (code "77") (name "unconnected-(U$26-PadA14{slash}DAC)") (class "Default")
      (node (ref "U$26") (pin "A14/DAC") (pinfunction "A14/DAC_A14/DAC") (pintype "bidirectional"))
    )
    (net (code "78") (name "unconnected-(U$26-PadD8{slash}TX3{slash}DIN)") (class "Default")
      (node (ref "U$26") (pin "D8/TX3/DIN") (pinfunction "D8/TX3/DIN_D8/TX3/DIN") (pintype "bidirectional"))
    )
    (net (code "79") (name "unconnected-(U$26-PadD24)") (class "Default")
      (node (ref "U$26") (pin "D24") (pinfunction "D24_D24") (pintype "bidirectional"))
    )
    (net (code "80") (name "unconnected-(U$26-PadD25{slash}TOUCH)") (class "Default")
      (node (ref "U$26") (pin "D25/TOUCH") (pinfunction "D25/TOUCH_D25/TOUCH") (pintype "bidirectional"))
    )
    (net (code "81") (name "unconnected-(U$26-PadPROGRAM)") (class "Default")
      (node (ref "U$26") (pin "PROGRAM") (pinfunction "PROGRAM_PROGRAM") (pintype "bidirectional"))
    )
    (net (code "82") (name "unconnected-(U$26-PadVBAT)") (class "Default")
      (node (ref "U$26") (pin "VBAT") (pinfunction "VBAT_VBAT") (pintype "bidirectional"))
    )
    (net (code "83") (name "unconnected-(U$26-PadVIN)") (class "Default")
      (node (ref "U$26") (pin "VIN") (pinfunction "VIN_VIN") (pintype "bidirectional"))
    )
    (net (code "84") (name "unconnected-(U$26-PadVUSB)") (class "Default")
      (node (ref "U$26") (pin "VUSB") (pinfunction "VUSB_VUSB") (pintype "bidirectional"))
    )
  )
)
